# Sheet1.net
KiCad netlist of a schematic drawn in Altium Designer
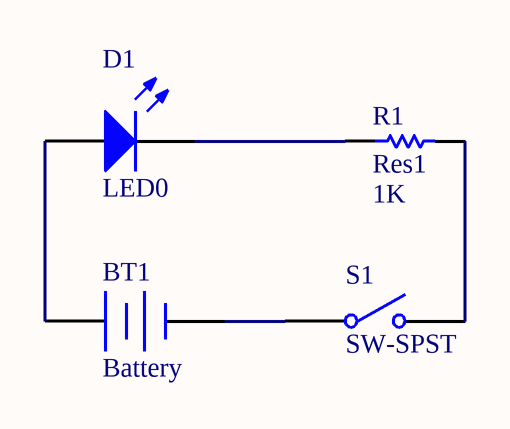
[diagram p0: Sheet1.SchDoc]

(export (version "E")
  (design (tool "Eeschema 10.0.6"))
  (components
    (comp (ref "BT1")
      (value "Battery")
      (footprint "BAT-2")
      (description "Multicell Battery")
      (fields (field (name "PUBLISHER") "Altium Limited"))
      (libsource (lib "Miscellaneous Devices") (part "Battery"))
    )
    (comp (ref "D1")
      (value "LED0")
      (footprint "LED-0")
      (description "Typical INFRARED GaAs LED")
      (fields (field (name "PUBLISHER") "Altium Limited"))
      (libsource (lib "Miscellaneous Devices") (part "LED0"))
    )
    (comp (ref "R1")
      (value "Res1")
      (footprint "AXIAL-0.3")
      (description "Resistor")
      (fields (field (name "ALTIUM_VALUE") "1K") (field (name "PUBLISHER") "Altium Limited"))
      (libsource (lib "Miscellaneous Devices") (part "Res1"))
    )
    (comp (ref "S1")
      (value "SW-SPST")
      (footprint "SPST-2")
      (description "Single-Pole, Single-Throw Switch")
      (fields (field (name "PUBLISHER") "Altium Limited"))
      (libsource (lib "Miscellaneous Devices") (part "SW-SPST"))
    )
  )
  (nets
    (net (code "1") (name "Net-(BT1-+)") (class "Default")
      (node (ref "BT1") (pin "1") (pinfunction "+_1") (pintype "passive"))
      (node (ref "D1") (pin "1") (pinfunction "A_1") (pintype "passive"))
    )
    (net (code "2") (name "Net-(BT1--)") (class "Default")
      (node (ref "BT1") (pin "2") (pinfunction "-_2") (pintype "passive"))
      (node (ref "S1") (pin "1") (pinfunction "COMMON_1") (pintype "passive"))
    )
    (net (code "3") (name "Net-(D1-K)") (class "Default")
      (node (ref "D1") (pin "2") (pinfunction "K_2") (pintype "passive"))
      (node (ref "R1") (pin "1") (pinfunction "1_1") (pintype "passive"))
    )
    (net (code "4") (name "Net-(S1-NO)") (class "Default")
      (node (ref "R1") (pin "2") (pinfunction "2_2") (pintype "passive"))
      (node (ref "S1") (pin "2") (pinfunction "NO_2") (pintype "passive"))
    )
  )
)
